# LEDs.net
KiCad netlist of a schematic drawn in Altium Designer
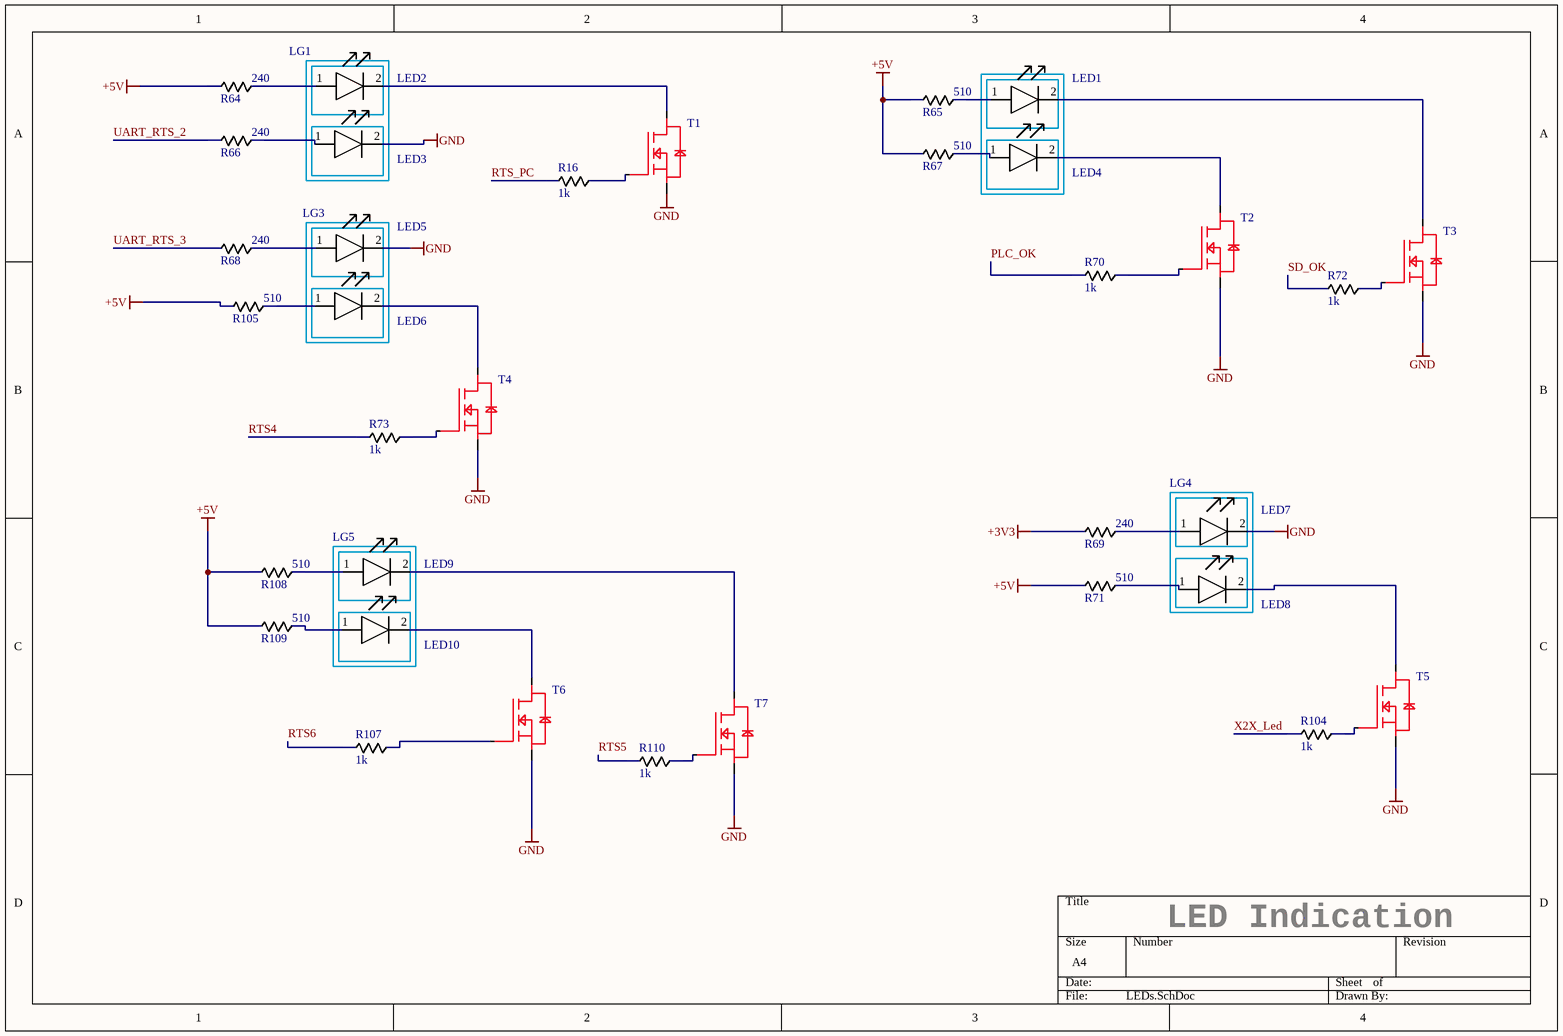
[diagram p0: LEDs.SchDoc]

(export (version "E")
  (design (tool "Eeschema 10.0.6"))
  (components
    (comp (ref "LED1")
      (value "~")
      (footprint "0603 - LED")
      (fields (field (name "PART NUMBER") "KP-1608SGC"))
      (libsource (lib "МЦТР.00010572.00.001") (part "LED 0603"))
    )
    (comp (ref "LED2")
      (value "~")
      (footprint "0603 - LED")
      (fields (field (name "PART NUMBER") "KP-1608SYC"))
      (libsource (lib "МЦТР.00010572.00.001") (part "LED 0603"))
    )
    (comp (ref "LED3")
      (value "~")
      (footprint "0603 - LED")
      (fields (field (name "PART NUMBER") "KP-1608SYC"))
      (libsource (lib "МЦТР.00010572.00.001") (part "LED 0603"))
    )
    (comp (ref "LED4")
      (value "~")
      (footprint "0603 - LED")
      (fields (field (name "PART NUMBER") "KP-1608SGC"))
      (libsource (lib "МЦТР.00010572.00.001") (part "LED 0603"))
    )
    (comp (ref "LED5")
      (value "~")
      (footprint "0603 - LED")
      (fields (field (name "PART NUMBER") "KP-1608SYC"))
      (libsource (lib "МЦТР.00010572.00.001") (part "LED 0603"))
    )
    (comp (ref "LED6")
      (value "~")
      (footprint "0603 - LED")
      (fields (field (name "PART NUMBER") "KP-1608SYC"))
      (libsource (lib "МЦТР.00010572.00.001") (part "LED 0603"))
    )
    (comp (ref "LED7")
      (value "~")
      (footprint "0603 - LED")
      (fields (field (name "PART NUMBER") "KP-1608SGC"))
      (libsource (lib "МЦТР.00010572.00.001") (part "LED 0603"))
    )
    (comp (ref "LED8")
      (value "~")
      (footprint "0603 - LED")
      (fields (field (name "PART NUMBER") "KP-1608SGC"))
      (libsource (lib "МЦТР.00010572.00.001") (part "LED 0603"))
    )
    (comp (ref "LED9")
      (value "~")
      (footprint "0603 - LED")
      (fields (field (name "PART NUMBER") "KP-1608SYC"))
      (libsource (lib "МЦТР.00010572.00.001") (part "LED 0603"))
    )
    (comp (ref "LED10")
      (value "~")
      (footprint "0603 - LED")
      (fields (field (name "PART NUMBER") "KP-1608SYC"))
      (libsource (lib "МЦТР.00010572.00.001") (part "LED 0603"))
    )
    (comp (ref "LG1")
      (value "~")
      (footprint "LED SMD DayLight")
      (fields (field (name "PART NUMBER") "5151094F"))
      (libsource (lib "МЦТР.00010572.00.001") (part "Light Guide 2"))
    )
    (comp (ref "LG2")
      (value "~")
      (footprint "LED SMD DayLight")
      (fields (field (name "PART NUMBER") "5151094F"))
      (libsource (lib "МЦТР.00010572.00.001") (part "Light Guide 2"))
    )
    (comp (ref "LG3")
      (value "1k")
      (footprint "LED SMD DayLight")
      (fields (field (name "PART NUMBER") "RC0603FR-071KL"))
      (libsource (lib "МЦТР.00010572.00.001") (part "Light Guide 2"))
    )
    (comp (ref "LG4")
      (value "~")
      (footprint "LED SMD DayLight")
      (fields (field (name "PART NUMBER") "5151094F"))
      (libsource (lib "МЦТР.00010572.00.001") (part "Light Guide 2"))
    )
    (comp (ref "LG5")
      (value "~")
      (footprint "LED SMD DayLight")
      (fields (field (name "PART NUMBER") "5151094F"))
      (libsource (lib "МЦТР.00010572.00.001") (part "Light Guide 2"))
    )
    (comp (ref "R16")
      (value "1k")
      (footprint "0603")
      (fields (field (name "PART NUMBER") "RC0603JR-071KL"))
      (libsource (lib "kontr") (part "Resistor 0805"))
    )
    (comp (ref "R64")
      (value "240")
      (footprint "0603")
      (fields (field (name "PART NUMBER") "RC0603FR-07240RL"))
      (libsource (lib "kontr") (part "Resistor 0805"))
    )
    (comp (ref "R65")
      (value "510")
      (footprint "0603")
      (fields (field (name "PART NUMBER") "RC0603JR-07510RL"))
      (libsource (lib "kontr") (part "Resistor 0805"))
    )
    (comp (ref "R66")
      (value "240")
      (footprint "0603")
      (fields (field (name "PART NUMBER") "RC0603FR-07240RL"))
      (libsource (lib "kontr") (part "Resistor 0805"))
    )
    (comp (ref "R67")
      (value "510")
      (footprint "0603")
      (fields (field (name "PART NUMBER") "RC0603JR-07510RL"))
      (libsource (lib "kontr") (part "Resistor 0805"))
    )
    (comp (ref "R68")
      (value "240")
      (footprint "0603")
      (fields (field (name "PART NUMBER") "RC0603FR-07240RL"))
      (libsource (lib "kontr") (part "Resistor 0805"))
    )
    (comp (ref "R69")
      (value "240")
      (footprint "0603")
      (fields (field (name "PART NUMBER") "RC0603FR-07240RL"))
      (libsource (lib "kontr") (part "Resistor 0805"))
    )
    (comp (ref "R70")
      (value "1k")
      (footprint "0603")
      (fields (field (name "PART NUMBER") "RC0603JR-071KL"))
      (libsource (lib "kontr") (part "Resistor 0805"))
    )
    (comp (ref "R71")
      (value "510")
      (footprint "0603")
      (fields (field (name "PART NUMBER") "RC0603JR-07510RL"))
      (libsource (lib "kontr") (part "Resistor 0805"))
    )
    (comp (ref "R72")
      (value "1k")
      (footprint "0603")
      (fields (field (name "PART NUMBER") "RC0603JR-071KL"))
      (libsource (lib "kontr") (part "Resistor 0805"))
    )
    (comp (ref "R73")
      (value "1k")
      (footprint "0603")
      (fields (field (name "PART NUMBER") "RC0603JR-071KL"))
      (libsource (lib "kontr") (part "Resistor 0805"))
    )
    (comp (ref "R104")
      (value "1k")
      (footprint "0603")
      (fields (field (name "PART NUMBER") "RC0603JR-071KL"))
      (libsource (lib "kontr") (part "Resistor 0805"))
    )
    (comp (ref "R105")
      (value "510")
      (footprint "0603")
      (fields (field (name "PART NUMBER") "RC0603JR-07510RL"))
      (libsource (lib "kontr") (part "Resistor 0805"))
    )
    (comp (ref "R107")
      (value "1k")
      (footprint "0603")
      (fields (field (name "PART NUMBER") "RC0603JR-071KL"))
      (libsource (lib "kontr") (part "Resistor 0805"))
    )
    (comp (ref "R108")
      (value "510")
      (footprint "0603")
      (fields (field (name "PART NUMBER") "RC0603JR-07510RL"))
      (libsource (lib "kontr") (part "Resistor 0805"))
    )
    (comp (ref "R109")
      (value "510")
      (footprint "0603")
      (fields (field (name "PART NUMBER") "RC0603JR-07510RL"))
      (libsource (lib "kontr") (part "Resistor 0805"))
    )
    (comp (ref "R110")
      (value "1k")
      (footprint "0603")
      (fields (field (name "PART NUMBER") "RC0603JR-071KL"))
      (libsource (lib "kontr") (part "Resistor 0805"))
    )
    (comp (ref "T1")
      (value "~")
      (footprint "SOT23")
      (fields (field (name "PART NUMBER") "BSS138"))
      (libsource (lib "kontr") (part "IRLML2402"))
    )
    (comp (ref "T2")
      (value "~")
      (footprint "SOT23")
      (fields (field (name "PART NUMBER") "BSS138"))
      (libsource (lib "kontr") (part "IRLML2402"))
    )
    (comp (ref "T3")
      (value "~")
      (footprint "SOT23")
      (fields (field (name "PART NUMBER") "BSS138"))
      (libsource (lib "kontr") (part "IRLML2402"))
    )
    (comp (ref "T4")
      (value "~")
      (footprint "SOT23")
      (fields (field (name "PART NUMBER") "BSS138"))
      (libsource (lib "kontr") (part "IRLML2402"))
    )
    (comp (ref "T5")
      (value "~")
      (footprint "SOT23")
      (fields (field (name "PART NUMBER") "BSS138"))
      (libsource (lib "kontr") (part "IRLML2402"))
    )
    (comp (ref "T6")
      (value "~")
      (footprint "SOT23")
      (fields (field (name "PART NUMBER") "BSS138"))
      (libsource (lib "kontr") (part "IRLML2402"))
    )
    (comp (ref "T7")
      (value "~")
      (footprint "SOT23")
      (fields (field (name "PART NUMBER") "BSS138"))
      (libsource (lib "kontr") (part "IRLML2402"))
    )
  )
  (nets
    (net (code "1") (name "+3V3") (class "Default") (node (ref "R69") (pin "2") (pintype "passive")))
    (net (code "2") (name "+5V") (class "Default")
      (node (ref "R105") (pin "2") (pintype "passive"))
      (node (ref "R108") (pin "2") (pintype "passive"))
      (node (ref "R109") (pin "2") (pintype "passive"))
      (node (ref "R64") (pin "2") (pintype "passive"))
      (node (ref "R65") (pin "2") (pintype "passive"))
      (node (ref "R67") (pin "2") (pintype "passive"))
      (node (ref "R71") (pin "2") (pintype "passive"))
    )
    (net (code "3") (name "/PLC_OK") (class "Default") (node (ref "R70") (pin "2") (pintype "passive")))
    (net (code "4") (name "/RTS4") (class "Default") (node (ref "R73") (pin "2") (pintype "passive")))
    (net (code "5") (name "/RTS5") (class "Default") (node (ref "R110") (pin "2") (pintype "passive")))
    (net (code "6") (name "/RTS6") (class "Default") (node (ref "R107") (pin "2") (pintype "passive")))
    (net (code "7") (name "/RTS_PC") (class "Default") (node (ref "R16") (pin "2") (pintype "passive")))
    (net (code "8") (name "/SD_OK") (class "Default") (node (ref "R72") (pin "2") (pintype "passive")))
    (net (code "9") (name "/UART_RTS_2") (class "Default") (node (ref "R66") (pin "2") (pintype "passive")))
    (net (code "10") (name "/UART_RTS_3") (class "Default") (node (ref "R68") (pin "2") (pintype "passive")))
    (net (code "11") (name "/X2X_Led") (class "Default") (node (ref "R104") (pin "2") (pintype "passive")))
    (net (code "12") (name "GND") (class "Default")
      (node (ref "LED3") (pin "2") (pintype "passive"))
      (node (ref "LED5") (pin "2") (pintype "passive"))
      (node (ref "LED7") (pin "2") (pintype "passive"))
      (node (ref "T1") (pin "2") (pinfunction "2_2") (pintype "passive"))
      (node (ref "T2") (pin "2") (pinfunction "2_2") (pintype "passive"))
      (node (ref "T3") (pin "2") (pinfunction "2_2") (pintype "passive"))
      (node (ref "T4") (pin "2") (pinfunction "2_2") (pintype "passive"))
      (node (ref "T5") (pin "2") (pinfunction "2_2") (pintype "passive"))
      (node (ref "T6") (pin "2") (pinfunction "2_2") (pintype "passive"))
      (node (ref "T7") (pin "2") (pinfunction "2_2") (pintype "passive"))
    )
    (net (code "13") (name "Net-(LED1-Pad1)") (class "Default")
      (node (ref "LED1") (pin "1") (pintype "passive"))
      (node (ref "R65") (pin "1") (pintype "passive"))
    )
    (net (code "14") (name "Net-(LED1-Pad2)") (class "Default")
      (node (ref "LED1") (pin "2") (pintype "passive"))
      (node (ref "T3") (pin "3") (pinfunction "3_3") (pintype "passive"))
    )
    (net (code "15") (name "Net-(LED2-Pad1)") (class "Default")
      (node (ref "LED2") (pin "1") (pintype "passive"))
      (node (ref "R64") (pin "1") (pintype "passive"))
    )
    (net (code "16") (name "Net-(LED2-Pad2)") (class "Default")
      (node (ref "LED2") (pin "2") (pintype "passive"))
      (node (ref "T1") (pin "3") (pinfunction "3_3") (pintype "passive"))
    )
    (net (code "17") (name "Net-(LED3-Pad1)") (class "Default")
      (node (ref "LED3") (pin "1") (pintype "passive"))
      (node (ref "R66") (pin "1") (pintype "passive"))
    )
    (net (code "18") (name "Net-(LED4-Pad1)") (class "Default")
      (node (ref "LED4") (pin "1") (pintype "passive"))
      (node (ref "R67") (pin "1") (pintype "passive"))
    )
    (net (code "19") (name "Net-(LED4-Pad2)") (class "Default")
      (node (ref "LED4") (pin "2") (pintype "passive"))
      (node (ref "T2") (pin "3") (pinfunction "3_3") (pintype "passive"))
    )
    (net (code "20") (name "Net-(LED5-Pad1)") (class "Default")
      (node (ref "LED5") (pin "1") (pintype "passive"))
      (node (ref "R68") (pin "1") (pintype "passive"))
    )
    (net (code "21") (name "Net-(LED6-Pad1)") (class "Default")
      (node (ref "LED6") (pin "1") (pintype "passive"))
      (node (ref "R105") (pin "1") (pintype "passive"))
    )
    (net (code "22") (name "Net-(LED6-Pad2)") (class "Default")
      (node (ref "LED6") (pin "2") (pintype "passive"))
      (node (ref "T4") (pin "3") (pinfunction "3_3") (pintype "passive"))
    )
    (net (code "23") (name "Net-(LED7-Pad1)") (class "Default")
      (node (ref "LED7") (pin "1") (pintype "passive"))
      (node (ref "R69") (pin "1") (pintype "passive"))
    )
    (net (code "24") (name "Net-(LED8-Pad1)") (class "Default")
      (node (ref "LED8") (pin "1") (pintype "passive"))
      (node (ref "R71") (pin "1") (pintype "passive"))
    )
    (net (code "25") (name "Net-(LED8-Pad2)") (class "Default")
      (node (ref "LED8") (pin "2") (pintype "passive"))
      (node (ref "T5") (pin "3") (pinfunction "3_3") (pintype "passive"))
    )
    (net (code "26") (name "Net-(LED9-Pad1)") (class "Default")
      (node (ref "LED9") (pin "1") (pintype "passive"))
      (node (ref "R108") (pin "1") (pintype "passive"))
    )
    (net (code "27") (name "Net-(LED9-Pad2)") (class "Default")
      (node (ref "LED9") (pin "2") (pintype "passive"))
      (node (ref "T7") (pin "3") (pinfunction "3_3") (pintype "passive"))
    )
    (net (code "28") (name "Net-(LED10-Pad1)") (class "Default")
      (node (ref "LED10") (pin "1") (pintype "passive"))
      (node (ref "R109") (pin "1") (pintype "passive"))
    )
    (net (code "29") (name "Net-(LED10-Pad2)") (class "Default")
      (node (ref "LED10") (pin "2") (pintype "passive"))
      (node (ref "T6") (pin "3") (pinfunction "3_3") (pintype "passive"))
    )
    (net (code "30") (name "Net-(R16-Pad1)") (class "Default")
      (node (ref "R16") (pin "1") (pintype "passive"))
      (node (ref "T1") (pin "1") (pinfunction "1_1") (pintype "passive"))
    )
    (net (code "31") (name "Net-(R70-Pad1)") (class "Default")
      (node (ref "R70") (pin "1") (pintype "passive"))
      (node (ref "T2") (pin "1") (pinfunction "1_1") (pintype "passive"))
    )
    (net (code "32") (name "Net-(R72-Pad1)") (class "Default")
      (node (ref "R72") (pin "1") (pintype "passive"))
      (node (ref "T3") (pin "1") (pinfunction "1_1") (pintype "passive"))
    )
    (net (code "33") (name "Net-(R73-Pad1)") (class "Default")
      (node (ref "R73") (pin "1") (pintype "passive"))
      (node (ref "T4") (pin "1") (pinfunction "1_1") (pintype "passive"))
    )
    (net (code "34") (name "Net-(R104-Pad1)") (class "Default")
      (node (ref "R104") (pin "1") (pintype "passive"))
      (node (ref "T5") (pin "1") (pinfunction "1_1") (pintype "passive"))
    )
    (net (code "35") (name "Net-(R107-Pad1)") (class "Default")
      (node (ref "R107") (pin "1") (pintype "passive"))
      (node (ref "T6") (pin "1") (pinfunction "1_1") (pintype "passive"))
    )
    (net (code "36") (name "Net-(R110-Pad1)") (class "Default")
      (node (ref "R110") (pin "1") (pintype "passive"))
      (node (ref "T7") (pin "1") (pinfunction "1_1") (pintype "passive"))
    )
  )
)
